# Power_Supply.net
KiCad netlist of a schematic drawn in Altium Designer
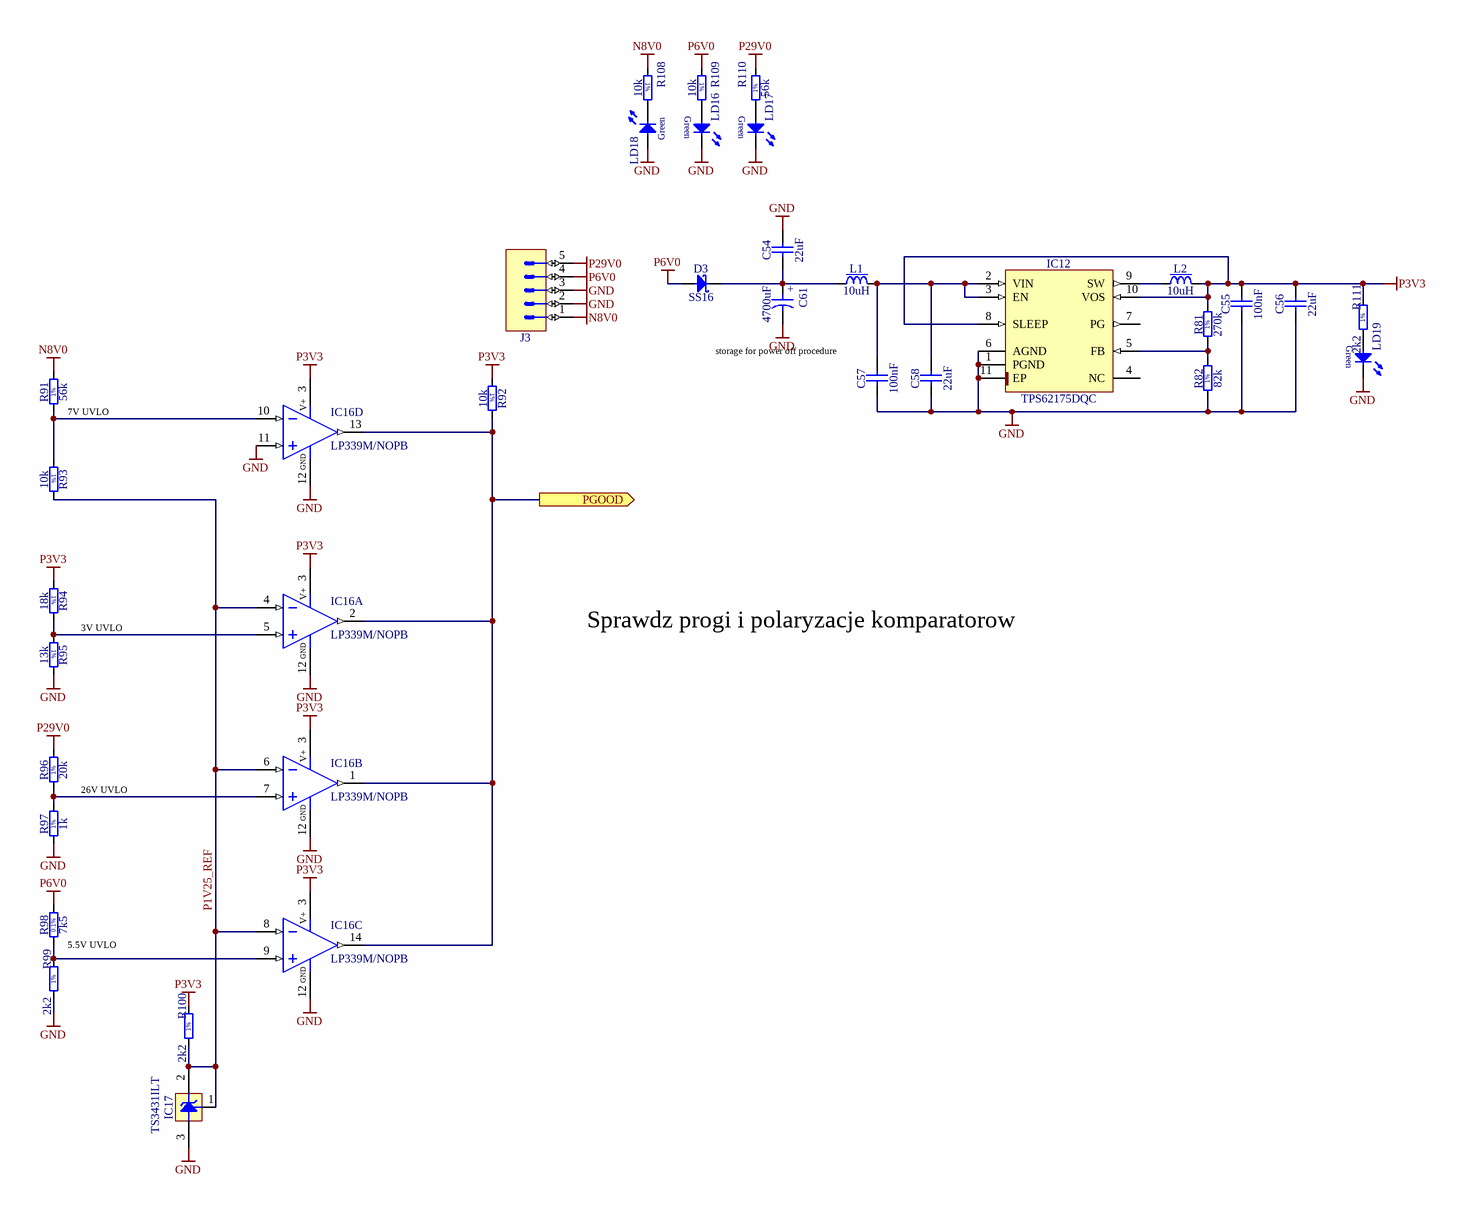
[diagram p0: Power_Supply.SchDoc]

(export (version "E")
  (design (tool "Eeschema 10.0.6"))
  (components
    (comp (ref "C54")
      (value "22uF")
      (footprint "CAPC2012X135N")
      (description "Non-polarised capacitor")
      (fields
        (field (name "PART NUMBER") "CC0805_22UF_16V_10%_X5R")
        (field (name "VOLTAGE") "16V")
        (field (name "AUTHOR") "CERN DEM JLC")
      )
      (libsource (lib "Capacitors") (part "Capacitor - non polarized"))
    )
    (comp (ref "C55")
      (value "100nF")
      (footprint "CAPC1005X55N")
      (description "Non-polarised capacitor")
      (fields
        (field (name "PART NUMBER") "CC0402_100NF_16V_10%_X5R")
        (field (name "VOLTAGE") "16V")
        (field (name "AUTHOR") "CERN DEM JLC")
      )
      (libsource (lib "Capacitors") (part "Capacitor - non polarized"))
    )
    (comp (ref "C56")
      (value "22uF")
      (footprint "CAPC2012X135N")
      (description "Non-polarised capacitor")
      (fields
        (field (name "PART NUMBER") "CC0805_22UF_16V_10%_X5R")
        (field (name "VOLTAGE") "16V")
        (field (name "AUTHOR") "CERN DEM JLC")
      )
      (libsource (lib "Capacitors") (part "Capacitor - non polarized"))
    )
    (comp (ref "C57")
      (value "100nF")
      (footprint "CAPC1005X55N")
      (description "Non-polarised capacitor")
      (fields
        (field (name "PART NUMBER") "CC0402_100NF_16V_10%_X5R")
        (field (name "VOLTAGE") "16V")
        (field (name "AUTHOR") "CERN DEM JLC")
      )
      (libsource (lib "Capacitors") (part "Capacitor - non polarized"))
    )
    (comp (ref "C58")
      (value "22uF")
      (footprint "CAPC2012X135N")
      (description "Non-polarised capacitor")
      (fields
        (field (name "PART NUMBER") "CC0805_22UF_16V_10%_X5R")
        (field (name "VOLTAGE") "16V")
        (field (name "AUTHOR") "CERN DEM JLC")
      )
      (libsource (lib "Capacitors") (part "Capacitor - non polarized"))
    )
    (comp (ref "C61")
      (value "4700uF")
      (footprint "CAPAE1900X1680N")
      (description "Polarised capacitor")
      (fields
        (field (name "PART NUMBER") "CAE1900-1680_4700UF_16V_20%")
        (field (name "VOLTAGE") "16V")
        (field (name "AUTHOR") "CERN DEM JLC")
      )
      (libsource (lib "Capacitors") (part "Capacitor - polarized"))
    )
    (comp (ref "D3")
      (value "SS16")
      (footprint "DIOM5127X229N")
      (description "Schottky Diode")
      (fields
        (field (name "VOLTAGE") "60V")
        (field (name "POWER") "1A")
        (field (name "AUTHOR") "CERN DEM JLC")
      )
      (libsource (lib "ICs And Semiconductors") (part "Diode Schottky"))
    )
    (comp (ref "IC12")
      (value "TPS62175DQC")
      (footprint "SON50P200X300X80-11N-R94X250")
      (description "4.75-28VDC to 1-6VDC, 500mA Step-Down Converter With Sleep Mode")
      (fields (field (name "MANUFACTURER") "TEXAS INSTRUMENTS") (field (name "AUTHOR") "CERN DEM JMW"))
      (libsource (lib "ICs And Semiconductors") (part "TPS62175"))
    )
    (comp (ref "IC16")
      (value "LP339M/NOPB")
      (footprint "SOIC127P600X175-14N")
      (description "Quad Operational Amplifier")
      (fields (field (name "MANUFACTURER") "TEXAS INSTRUMENTS") (field (name "AUTHOR") "CERN DEM MR"))
      (libsource (lib "ICs And Semiconductors") (part "Operational Amplifier x4 Type5"))
    )
    (comp (ref "IC17")
      (value "TS3431ILT")
      (footprint "SOT95P237X112-3N")
      (description "Precision Reference 1=Adj 2=Cathode 3=Anode")
      (fields (field (name "MANUFACTURER") "ST MICROELECTRONICS") (field (name "AUTHOR") "CERN DEM JLC"))
      (libsource (lib "ICs And Semiconductors") (part "VREF 1ADJ-2C-3A"))
    )
    (comp (ref "J3")
      (value "~")
      (footprint "PHOENIX_1755765")
      (description "Connector 5 Male")
      (fields
        (field (name "PART NUMBER") "PHOENIX_1755765")
        (field (name "MANUFACTURER") "PHOENIX CONTACT")
        (field (name "AUTHOR") "CERN DEM JLC")
      )
      (libsource (lib "Connectors") (part "Connector 5 Male"))
    )
    (comp (ref "L1")
      (value "10uH")
      (footprint "IND_MURATA-PS_8400")
      (description "Inductor With Core")
      (fields
        (field (name "PART NUMBER") "IND_10UH_10%_MURATA-PS_8400")
        (field (name "POWER") "950mA")
        (field (name "AUTHOR") "CERN DEM JLC")
      )
      (libsource (lib "Inductors & Transformers") (part "Inductor With Magnetic core"))
    )
    (comp (ref "L2")
      (value "10uH")
      (footprint "IND_MURATA-PS_8400")
      (description "Inductor With Core")
      (fields
        (field (name "PART NUMBER") "IND_10UH_10%_MURATA-PS_8400")
        (field (name "POWER") "950mA")
        (field (name "AUTHOR") "CERN DEM JLC")
      )
      (libsource (lib "Inductors & Transformers") (part "Inductor With Magnetic core"))
    )
    (comp (ref "LD16")
      (value "Green")
      (footprint "LED_OSRAM_LGL29K")
      (description "LED Green 1C 2A")
      (fields
        (field (name "PART NUMBER") "LED_OSRAM_LG L29K-G2J1-24-Z")
        (field (name "MANUFACTURER") "OSRAM")
        (field (name "AUTHOR") "CERN DEM JLC")
      )
      (libsource (lib "ICs And Semiconductors") (part "LED Green 1C 2A"))
    )
    (comp (ref "LD17")
      (value "Green")
      (footprint "LED_OSRAM_LGL29K")
      (description "LED Green 1C 2A")
      (fields
        (field (name "PART NUMBER") "LED_OSRAM_LG L29K-G2J1-24-Z")
        (field (name "MANUFACTURER") "OSRAM")
        (field (name "AUTHOR") "CERN DEM JLC")
      )
      (libsource (lib "ICs And Semiconductors") (part "LED Green 1C 2A"))
    )
    (comp (ref "LD18")
      (value "Green")
      (footprint "LED_OSRAM_LGL29K")
      (description "LED Green 1C 2A")
      (fields
        (field (name "PART NUMBER") "LED_OSRAM_LG L29K-G2J1-24-Z")
        (field (name "MANUFACTURER") "OSRAM")
        (field (name "AUTHOR") "CERN DEM JLC")
      )
      (libsource (lib "ICs And Semiconductors") (part "LED Green 1C 2A"))
    )
    (comp (ref "LD19")
      (value "Green")
      (footprint "LED_OSRAM_LGL29K")
      (description "LED Green 1C 2A")
      (fields
        (field (name "PART NUMBER") "LED_OSRAM_LG L29K-G2J1-24-Z")
        (field (name "MANUFACTURER") "OSRAM")
        (field (name "AUTHOR") "CERN DEM JLC")
      )
      (libsource (lib "ICs And Semiconductors") (part "LED Green 1C 2A"))
    )
    (comp (ref "R81")
      (value "270k")
      (footprint "RESC1608X55N")
      (description "Resistor - 1%")
      (fields
        (field (name "PART NUMBER") "R0603_270K_1%_0.1W_100PPM")
        (field (name "POWER") "0.1W")
        (field (name "AUTHOR") "CERN DEM JLC")
      )
      (libsource (lib "Resistors") (part "Resistor - 1%"))
    )
    (comp (ref "R82")
      (value "82k")
      (footprint "RESC1608X55N")
      (description "Resistor - 1%")
      (fields
        (field (name "PART NUMBER") "R0603_82K_1%_0.1W_100PPM")
        (field (name "POWER") "0.1W")
        (field (name "AUTHOR") "CERN DEM JLC")
      )
      (libsource (lib "Resistors") (part "Resistor - 1%"))
    )
    (comp (ref "R91")
      (value "56k")
      (footprint "RESC1608X55N")
      (description "Resistor - 1%")
      (fields
        (field (name "PART NUMBER") "R0603_56K_1%_0.1W_100PPM")
        (field (name "POWER") "0.1W")
        (field (name "AUTHOR") "CERN DEM JLC")
      )
      (libsource (lib "Resistors") (part "Resistor - 1%"))
    )
    (comp (ref "R92")
      (value "10k")
      (footprint "RESC1005X40N")
      (description "Resistor - 1%")
      (fields
        (field (name "PART NUMBER") "R0402_10K_1%_0.0625W_100PPM")
        (field (name "POWER") "0.0625W")
        (field (name "AUTHOR") "CERN DEM JLC")
      )
      (libsource (lib "Resistors") (part "Resistor - 1%"))
    )
    (comp (ref "R93")
      (value "10k")
      (footprint "RESC1005X40N")
      (description "Resistor - 1%")
      (fields
        (field (name "PART NUMBER") "R0402_10K_1%_0.0625W_100PPM")
        (field (name "POWER") "0.0625W")
        (field (name "AUTHOR") "CERN DEM JLC")
      )
      (libsource (lib "Resistors") (part "Resistor - 1%"))
    )
    (comp (ref "R94")
      (value "18k")
      (footprint "RESC1608X55N")
      (description "Resistor - 1%")
      (fields
        (field (name "PART NUMBER") "R0603_18K_1%_0.1W_100PPM")
        (field (name "POWER") "0.1W")
        (field (name "AUTHOR") "CERN DEM JLC")
      )
      (libsource (lib "Resistors") (part "Resistor - 1%"))
    )
    (comp (ref "R95")
      (value "13k")
      (footprint "RESC1608X55N")
      (description "Resistor - 1%")
      (fields
        (field (name "PART NUMBER") "R0603_13K_1%_0.1W_100PPM")
        (field (name "POWER") "0.1W")
        (field (name "AUTHOR") "CERN DEM JLC")
      )
      (libsource (lib "Resistors") (part "Resistor - 1%"))
    )
    (comp (ref "R96")
      (value "20k")
      (footprint "RESC1608X55N")
      (description "Resistor - 1%")
      (fields
        (field (name "PART NUMBER") "R0603_20K_1%_0.1W_100PPM")
        (field (name "POWER") "0.1W")
        (field (name "AUTHOR") "CERN DEM JLC")
      )
      (libsource (lib "Resistors") (part "Resistor - 1%"))
    )
    (comp (ref "R97")
      (value "1k")
      (footprint "RESC1608X55N")
      (description "Resistor - 1%")
      (fields
        (field (name "PART NUMBER") "R0603_1K_1%_0.1W_100PPM")
        (field (name "POWER") "0.1W")
        (field (name "AUTHOR") "CERN DEM JLC")
      )
      (libsource (lib "Resistors") (part "Resistor - 1%"))
    )
    (comp (ref "R98")
      (value "7k5")
      (footprint "RESC1608X55N")
      (description "Resistor - 0.1%")
      (fields
        (field (name "PART NUMBER") "R0603_7K5_0.1%_0.063W_10PPM")
        (field (name "POWER") "0.063W")
        (field (name "AUTHOR") "CERN DEM JLC")
      )
      (libsource (lib "Resistors") (part "Resistor - 0.1%"))
    )
    (comp (ref "R99")
      (value "2k2")
      (footprint "RESC1005X40N")
      (description "Resistor - 1%")
      (fields
        (field (name "PART NUMBER") "R0402_2K2_1%_0.0625W_100PPM")
        (field (name "POWER") "0.0625W")
        (field (name "AUTHOR") "CERN DEM JLC")
      )
      (libsource (lib "Resistors") (part "Resistor - 1%"))
    )
    (comp (ref "R100")
      (value "2k2")
      (footprint "RESC1005X40N")
      (description "Resistor - 1%")
      (fields
        (field (name "PART NUMBER") "R0402_2K2_1%_0.0625W_100PPM")
        (field (name "POWER") "0.0625W")
        (field (name "AUTHOR") "CERN DEM JLC")
      )
      (libsource (lib "Resistors") (part "Resistor - 1%"))
    )
    (comp (ref "R108")
      (value "10k")
      (footprint "RESC1005X40N")
      (description "Resistor - 1%")
      (fields
        (field (name "PART NUMBER") "R0402_10K_1%_0.0625W_100PPM")
        (field (name "POWER") "0.0625W")
        (field (name "AUTHOR") "CERN DEM JLC")
      )
      (libsource (lib "Resistors") (part "Resistor - 1%"))
    )
    (comp (ref "R109")
      (value "10k")
      (footprint "RESC1005X40N")
      (description "Resistor - 1%")
      (fields
        (field (name "PART NUMBER") "R0402_10K_1%_0.0625W_100PPM")
        (field (name "POWER") "0.0625W")
        (field (name "AUTHOR") "CERN DEM JLC")
      )
      (libsource (lib "Resistors") (part "Resistor - 1%"))
    )
    (comp (ref "R110")
      (value "56k")
      (footprint "RESC1608X55N")
      (description "Resistor - 1%")
      (fields
        (field (name "PART NUMBER") "R0603_56K_1%_0.1W_100PPM")
        (field (name "POWER") "0.1W")
        (field (name "AUTHOR") "CERN DEM JLC")
      )
      (libsource (lib "Resistors") (part "Resistor - 1%"))
    )
    (comp (ref "R111")
      (value "2k2")
      (footprint "RESC1005X40N")
      (description "Resistor - 1%")
      (fields
        (field (name "PART NUMBER") "R0402_2K2_1%_0.0625W_100PPM")
        (field (name "POWER") "0.0625W")
        (field (name "AUTHOR") "CERN DEM JLC")
      )
      (libsource (lib "Resistors") (part "Resistor - 1%"))
    )
  )
  (nets
    (net (code "1") (name "/P1V25_REF") (class "Default")
      (node (ref "IC16") (pin "4") (pinfunction "IN-_4") (pintype "input"))
      (node (ref "IC16") (pin "6") (pinfunction "IN-_6") (pintype "input"))
      (node (ref "IC16") (pin "8") (pinfunction "IN-_8") (pintype "input"))
      (node (ref "IC17") (pin "1") (pinfunction "Adj_1") (pintype "passive"))
      (node (ref "IC17") (pin "2") (pinfunction "C_2") (pintype "passive"))
      (node (ref "R100") (pin "1") (pinfunction "1_1") (pintype "passive"))
      (node (ref "R93") (pin "2") (pinfunction "2_2") (pintype "passive"))
    )
    (net (code "2") (name "/PGOOD") (class "Default")
      (node (ref "IC16") (pin "1") (pinfunction "OUT_1") (pintype "output"))
      (node (ref "IC16") (pin "13") (pinfunction "OUT_13") (pintype "output"))
      (node (ref "IC16") (pin "14") (pinfunction "OUT_14") (pintype "output"))
      (node (ref "IC16") (pin "2") (pinfunction "OUT_2") (pintype "output"))
      (node (ref "R92") (pin "2") (pinfunction "2_2") (pintype "passive"))
    )
    (net (code "3") (name "GND") (class "Default")
      (node (ref "C54") (pin "2") (pinfunction "2_2") (pintype "passive"))
      (node (ref "C55") (pin "1") (pinfunction "1_1") (pintype "passive"))
      (node (ref "C56") (pin "1") (pinfunction "1_1") (pintype "passive"))
      (node (ref "C57") (pin "1") (pinfunction "1_1") (pintype "passive"))
      (node (ref "C58") (pin "1") (pinfunction "1_1") (pintype "passive"))
      (node (ref "C61") (pin "2") (pinfunction "2_2") (pintype "passive"))
      (node (ref "IC12") (pin "1") (pinfunction "PGND_1") (pintype "power_in"))
      (node (ref "IC12") (pin "11") (pinfunction "EP_11") (pintype "power_in"))
      (node (ref "IC12") (pin "6") (pinfunction "AGND_6") (pintype "power_in"))
      (node (ref "IC16") (pin "11") (pinfunction "IN+_11") (pintype "input"))
      (node (ref "IC16") (pin "12") (pinfunction "GND_12") (pintype "power_in"))
      (node (ref "IC17") (pin "3") (pinfunction "A_3") (pintype "passive"))
      (node (ref "J3") (pin "2") (pinfunction "2_2") (pintype "bidirectional"))
      (node (ref "J3") (pin "3") (pinfunction "3_3") (pintype "bidirectional"))
      (node (ref "LD16") (pin "1") (pinfunction "C_1") (pintype "passive"))
      (node (ref "LD17") (pin "1") (pinfunction "C_1") (pintype "passive"))
      (node (ref "LD18") (pin "2") (pinfunction "A_2") (pintype "passive"))
      (node (ref "LD19") (pin "1") (pinfunction "C_1") (pintype "passive"))
      (node (ref "R82") (pin "1") (pinfunction "1_1") (pintype "passive"))
      (node (ref "R95") (pin "2") (pinfunction "2_2") (pintype "passive"))
      (node (ref "R97") (pin "1") (pinfunction "1_1") (pintype "passive"))
      (node (ref "R99") (pin "1") (pinfunction "1_1") (pintype "passive"))
    )
    (net (code "4") (name "N8V0") (class "Default")
      (node (ref "J3") (pin "1") (pinfunction "1_1") (pintype "bidirectional"))
      (node (ref "R108") (pin "1") (pinfunction "1_1") (pintype "passive"))
      (node (ref "R91") (pin "2") (pinfunction "2_2") (pintype "passive"))
    )
    (net (code "5") (name "Net-(D3-C)") (class "Default")
      (node (ref "C54") (pin "1") (pinfunction "1_1") (pintype "passive"))
      (node (ref "C61") (pin "1") (pinfunction "1_1") (pintype "passive"))
      (node (ref "D3") (pin "1") (pinfunction "C_1") (pintype "passive"))
      (node (ref "L1") (pin "1") (pinfunction "1_1") (pintype "passive"))
    )
    (net (code "6") (name "Net-(IC12-EN)") (class "Default")
      (node (ref "C57") (pin "2") (pinfunction "2_2") (pintype "passive"))
      (node (ref "C58") (pin "2") (pinfunction "2_2") (pintype "passive"))
      (node (ref "IC12") (pin "2") (pinfunction "VIN_2") (pintype "input"))
      (node (ref "IC12") (pin "3") (pinfunction "EN_3") (pintype "input"))
      (node (ref "L1") (pin "2") (pinfunction "2_2") (pintype "passive"))
    )
    (net (code "7") (name "Net-(IC12-FB)") (class "Default")
      (node (ref "IC12") (pin "5") (pinfunction "FB_5") (pintype "input"))
      (node (ref "R81") (pin "1") (pinfunction "1_1") (pintype "passive"))
      (node (ref "R82") (pin "2") (pinfunction "2_2") (pintype "passive"))
    )
    (net (code "8") (name "Net-(IC12-SW)") (class "Default")
      (node (ref "IC12") (pin "9") (pinfunction "SW_9") (pintype "output"))
      (node (ref "L2") (pin "1") (pinfunction "1_1") (pintype "passive"))
    )
    (net (code "9") (name "Net-(IC16A-IN+)") (class "Default")
      (node (ref "IC16") (pin "5") (pinfunction "IN+_5") (pintype "input"))
      (node (ref "R94") (pin "2") (pinfunction "2_2") (pintype "passive"))
      (node (ref "R95") (pin "1") (pinfunction "1_1") (pintype "passive"))
    )
    (net (code "10") (name "Net-(IC16B-IN+)") (class "Default")
      (node (ref "IC16") (pin "7") (pinfunction "IN+_7") (pintype "input"))
      (node (ref "R96") (pin "1") (pinfunction "1_1") (pintype "passive"))
      (node (ref "R97") (pin "2") (pinfunction "2_2") (pintype "passive"))
    )
    (net (code "11") (name "Net-(IC16C-IN+)") (class "Default")
      (node (ref "IC16") (pin "9") (pinfunction "IN+_9") (pintype "input"))
      (node (ref "R98") (pin "1") (pinfunction "1_1") (pintype "passive"))
      (node (ref "R99") (pin "2") (pinfunction "2_2") (pintype "passive"))
    )
    (net (code "12") (name "Net-(IC16D-IN-)") (class "Default")
      (node (ref "IC16") (pin "10") (pinfunction "IN-_10") (pintype "input"))
      (node (ref "R91") (pin "1") (pinfunction "1_1") (pintype "passive"))
      (node (ref "R93") (pin "1") (pinfunction "1_1") (pintype "passive"))
    )
    (net (code "13") (name "Net-(LD16-A)") (class "Default")
      (node (ref "LD16") (pin "2") (pinfunction "A_2") (pintype "passive"))
      (node (ref "R109") (pin "2") (pinfunction "2_2") (pintype "passive"))
    )
    (net (code "14") (name "Net-(LD17-A)") (class "Default")
      (node (ref "LD17") (pin "2") (pinfunction "A_2") (pintype "passive"))
      (node (ref "R110") (pin "1") (pinfunction "1_1") (pintype "passive"))
    )
    (net (code "15") (name "Net-(LD18-C)") (class "Default")
      (node (ref "LD18") (pin "1") (pinfunction "C_1") (pintype "passive"))
      (node (ref "R108") (pin "2") (pinfunction "2_2") (pintype "passive"))
    )
    (net (code "16") (name "Net-(LD19-A)") (class "Default")
      (node (ref "LD19") (pin "2") (pinfunction "A_2") (pintype "passive"))
      (node (ref "R111") (pin "1") (pinfunction "1_1") (pintype "passive"))
    )
    (net (code "17") (name "P3V3") (class "Default")
      (node (ref "C55") (pin "2") (pinfunction "2_2") (pintype "passive"))
      (node (ref "C56") (pin "2") (pinfunction "2_2") (pintype "passive"))
      (node (ref "IC12") (pin "10") (pinfunction "VOS_10") (pintype "input"))
      (node (ref "IC12") (pin "8") (pinfunction "SLEEP_8") (pintype "input"))
      (node (ref "IC16") (pin "3") (pinfunction "V+_3") (pintype "power_in"))
      (node (ref "L2") (pin "2") (pinfunction "2_2") (pintype "passive"))
      (node (ref "R100") (pin "2") (pinfunction "2_2") (pintype "passive"))
      (node (ref "R111") (pin "2") (pinfunction "2_2") (pintype "passive"))
      (node (ref "R81") (pin "2") (pinfunction "2_2") (pintype "passive"))
      (node (ref "R92") (pin "1") (pinfunction "1_1") (pintype "passive"))
      (node (ref "R94") (pin "1") (pinfunction "1_1") (pintype "passive"))
    )
    (net (code "18") (name "P6V0") (class "Default")
      (node (ref "D3") (pin "2") (pinfunction "A_2") (pintype "passive"))
      (node (ref "J3") (pin "4") (pinfunction "4_4") (pintype "bidirectional"))
      (node (ref "R109") (pin "1") (pinfunction "1_1") (pintype "passive"))
      (node (ref "R98") (pin "2") (pinfunction "2_2") (pintype "passive"))
    )
    (net (code "19") (name "P29V0") (class "Default")
      (node (ref "J3") (pin "5") (pinfunction "5_5") (pintype "bidirectional"))
      (node (ref "R110") (pin "2") (pinfunction "2_2") (pintype "passive"))
      (node (ref "R96") (pin "2") (pinfunction "2_2") (pintype "passive"))
    )
    (net (code "20") (name "unconnected-(IC12-NC-Pad4)") (class "Default")
      (node (ref "IC12") (pin "4") (pinfunction "NC_4") (pintype "passive"))
    )
    (net (code "21") (name "unconnected-(IC12-PG-Pad7)") (class "Default")
      (node (ref "IC12") (pin "7") (pinfunction "PG_7") (pintype "output"))
    )
  )
)
